# StickSoc_Left.net
KiCad netlist of a schematic drawn in EAGLE
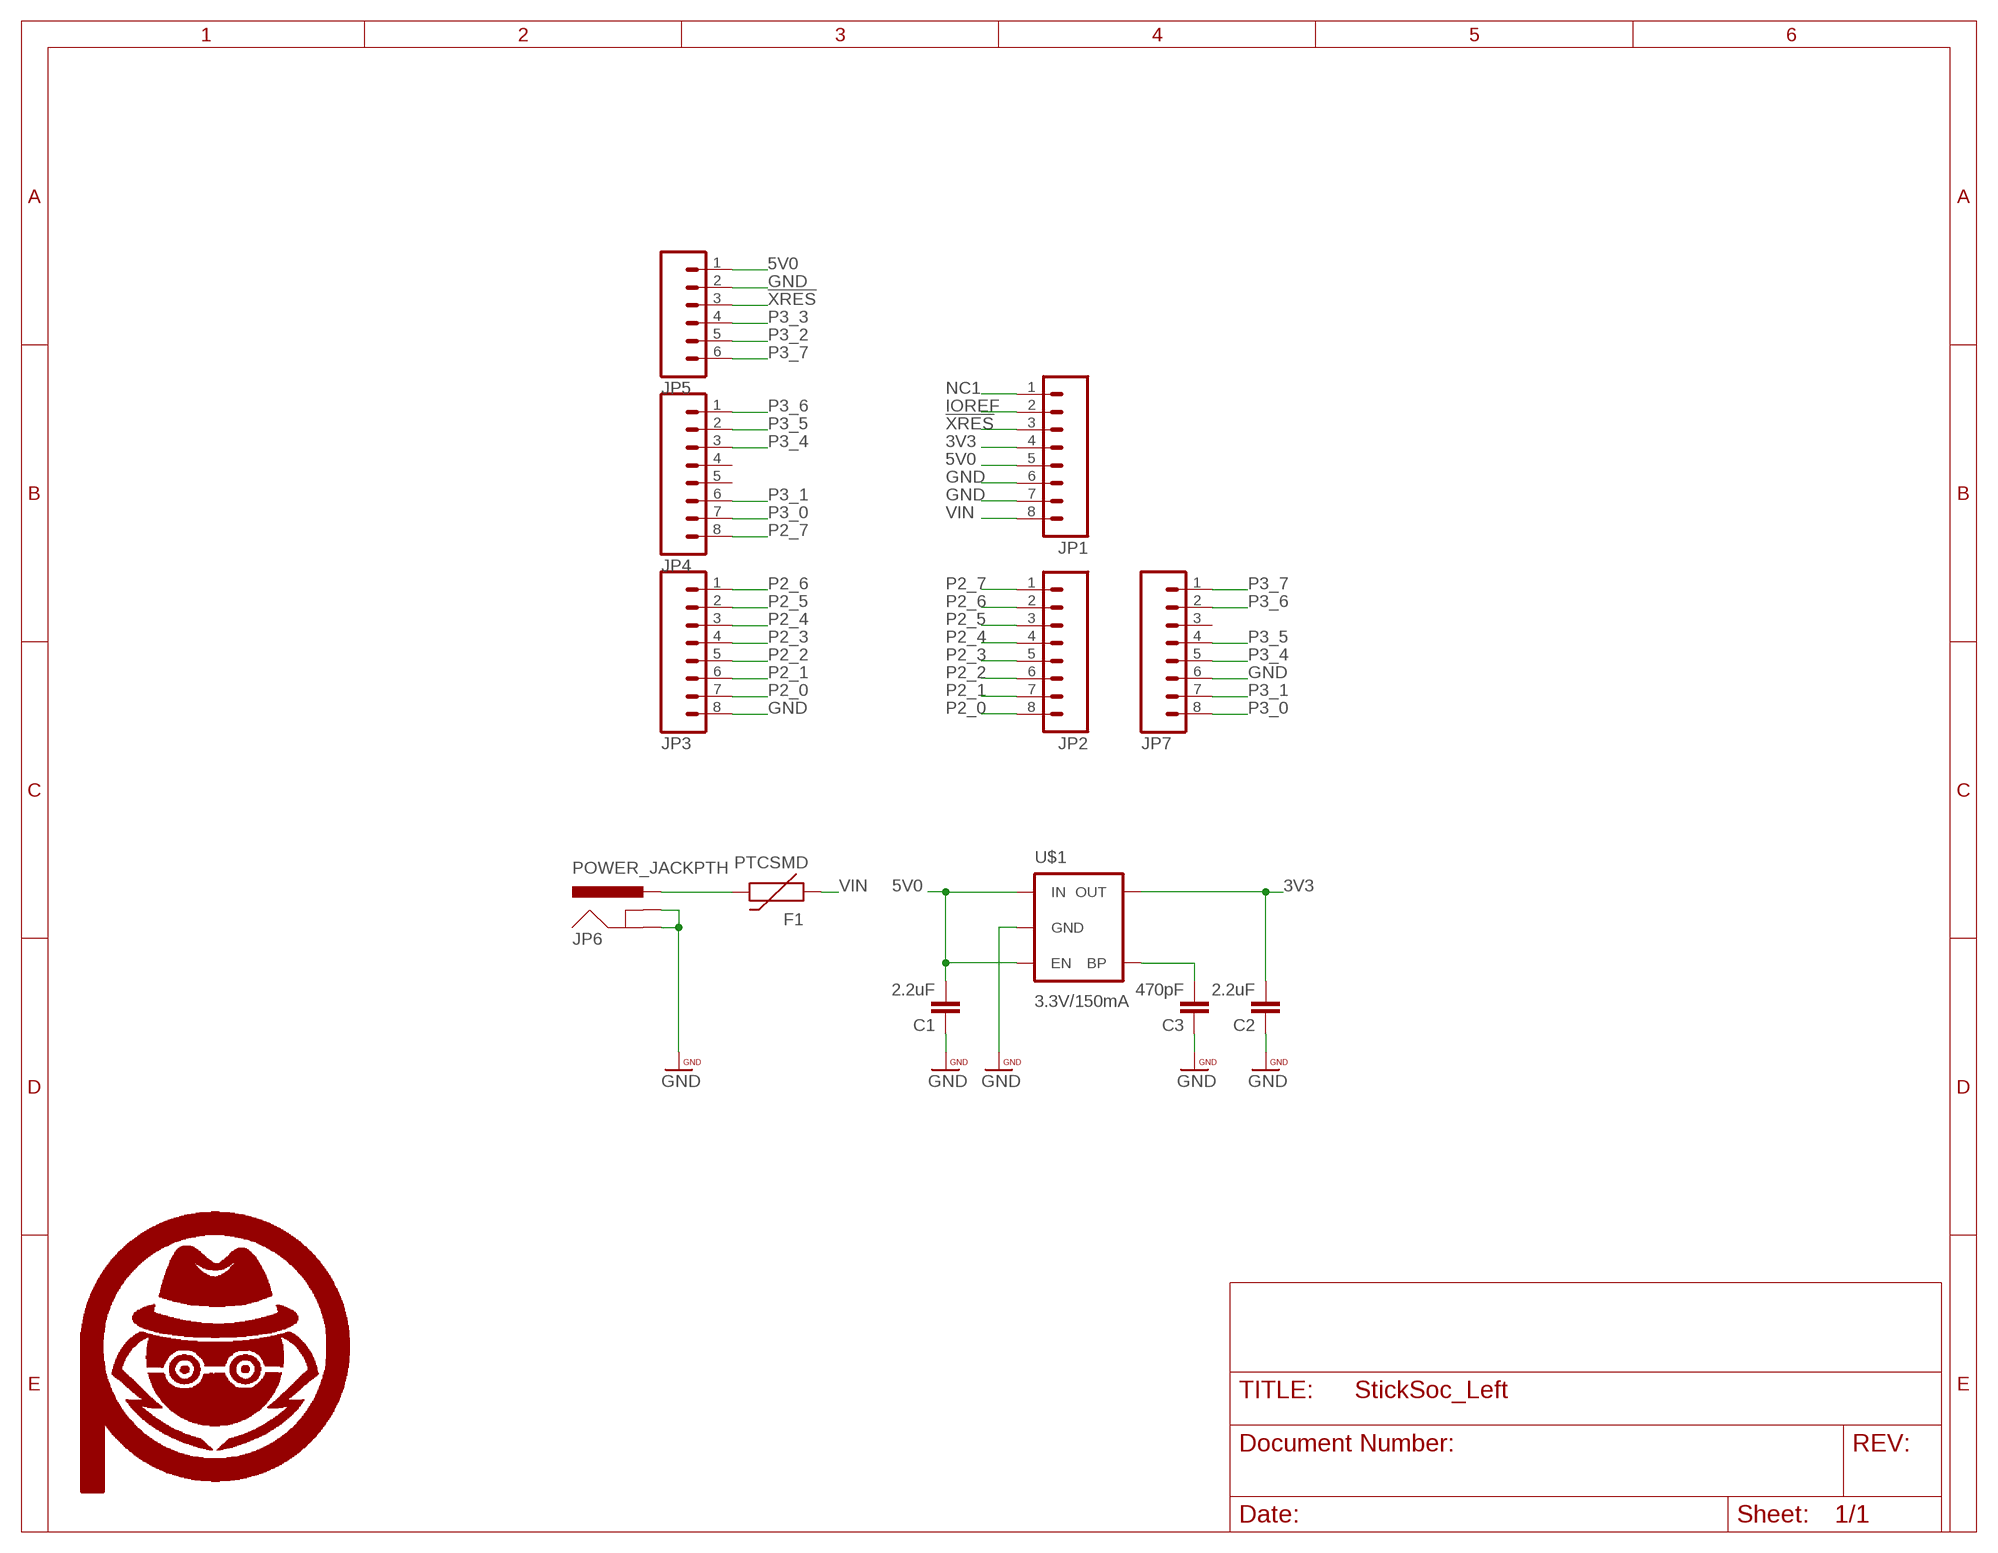
[diagram p0: schematic, sheet 1]

(export (version "E")
  (design (tool "Eeschema 10.0.6"))
  (components
    (comp (ref "C1")
      (value "2.2uF")
      (footprint "eagle-import:0805")
      (libsource (lib "eagle-import") (part "CAP0805"))
    )
    (comp (ref "C2")
      (value "2.2uF")
      (footprint "eagle-import:0805")
      (libsource (lib "eagle-import") (part "CAP0805"))
    )
    (comp (ref "C3")
      (value "470pF")
      (footprint "eagle-import:0805")
      (libsource (lib "eagle-import") (part "CAP0805"))
    )
    (comp (ref "F1")
      (value "PTCSMD")
      (footprint "eagle-import:PTC-1206")
      (libsource (lib "eagle-import") (part "PTCSMD"))
    )
    (comp (ref "JP1")
      (value "M081X08")
      (footprint "eagle-import:1X08")
      (libsource (lib "eagle-import") (part "M081X08"))
    )
    (comp (ref "JP2")
      (value "M081X08")
      (footprint "eagle-import:1X08")
      (libsource (lib "eagle-import") (part "M081X08"))
    )
    (comp (ref "JP3")
      (value "M081X08")
      (footprint "eagle-import:1X08")
      (libsource (lib "eagle-import") (part "M081X08"))
    )
    (comp (ref "JP4")
      (value "M081X08")
      (footprint "eagle-import:1X08")
      (libsource (lib "eagle-import") (part "M081X08"))
    )
    (comp (ref "JP5")
      (value "M06SIP")
      (footprint "eagle-import:1X06")
      (libsource (lib "eagle-import") (part "M06SIP"))
    )
    (comp (ref "JP6")
      (value "POWER_JACKPTH")
      (footprint "eagle-import:POWER_JACK_PTH")
      (libsource (lib "eagle-import") (part "POWER_JACKPTH"))
    )
    (comp (ref "JP7")
      (value "M081X08")
      (footprint "eagle-import:1X08")
      (libsource (lib "eagle-import") (part "M081X08"))
    )
    (comp (ref "U$1")
      (value "3.3V/150mA")
      (footprint "eagle-import:SOT23-5")
      (libsource (lib "eagle-import") (part "V_REG_MIC52053.3V"))
    )
    (comp (ref "U$7")
      (value "PA_LOGO_SYMSMALL")
      (footprint "eagle-import:PA_LOGO_AGENT_SMALL_SYM")
      (libsource (lib "eagle-import") (part "PA_LOGO_SYMSMALL"))
    )
    (comp (ref "U$8")
      (value "PA_LOGO_SYMSMALL")
      (footprint "eagle-import:PA_LOGO_AGENT_SMALL_SYM")
      (libsource (lib "eagle-import") (part "PA_LOGO_SYMSMALL"))
    )
  )
  (nets
    (net (code "1") (name "/3V3") (class "Default")
      (node (ref "C2") (pin "2") (pinfunction "2_2") (pintype "passive"))
      (node (ref "JP1") (pin "4") (pinfunction "4_4") (pintype "passive"))
      (node (ref "U$1") (pin "5") (pinfunction "OUT_5") (pintype "passive"))
    )
    (net (code "2") (name "/5V0") (class "Default")
      (node (ref "C1") (pin "2") (pinfunction "2_2") (pintype "passive"))
      (node (ref "JP1") (pin "5") (pinfunction "5_5") (pintype "passive"))
      (node (ref "JP5") (pin "1") (pinfunction "1_1") (pintype "passive"))
      (node (ref "U$1") (pin "1") (pinfunction "IN_1") (pintype "input"))
      (node (ref "U$1") (pin "3") (pinfunction "EN_3") (pintype "input"))
    )
    (net (code "3") (name "/IOREF") (class "Default")
      (node (ref "JP1") (pin "2") (pinfunction "2_2") (pintype "passive"))
    )
    (net (code "4") (name "/NC1") (class "Default")
      (node (ref "JP1") (pin "1") (pinfunction "1_1") (pintype "passive"))
    )
    (net (code "5") (name "/P2_0") (class "Default")
      (node (ref "JP2") (pin "8") (pinfunction "8_8") (pintype "passive"))
      (node (ref "JP3") (pin "7") (pinfunction "7_7") (pintype "passive"))
    )
    (net (code "6") (name "/P2_1") (class "Default")
      (node (ref "JP2") (pin "7") (pinfunction "7_7") (pintype "passive"))
      (node (ref "JP3") (pin "6") (pinfunction "6_6") (pintype "passive"))
    )
    (net (code "7") (name "/P2_2") (class "Default")
      (node (ref "JP2") (pin "6") (pinfunction "6_6") (pintype "passive"))
      (node (ref "JP3") (pin "5") (pinfunction "5_5") (pintype "passive"))
    )
    (net (code "8") (name "/P2_3") (class "Default")
      (node (ref "JP2") (pin "5") (pinfunction "5_5") (pintype "passive"))
      (node (ref "JP3") (pin "4") (pinfunction "4_4") (pintype "passive"))
    )
    (net (code "9") (name "/P2_4") (class "Default")
      (node (ref "JP2") (pin "4") (pinfunction "4_4") (pintype "passive"))
      (node (ref "JP3") (pin "3") (pinfunction "3_3") (pintype "passive"))
    )
    (net (code "10") (name "/P2_5") (class "Default")
      (node (ref "JP2") (pin "3") (pinfunction "3_3") (pintype "passive"))
      (node (ref "JP3") (pin "2") (pinfunction "2_2") (pintype "passive"))
    )
    (net (code "11") (name "/P2_6") (class "Default")
      (node (ref "JP2") (pin "2") (pinfunction "2_2") (pintype "passive"))
      (node (ref "JP3") (pin "1") (pinfunction "1_1") (pintype "passive"))
    )
    (net (code "12") (name "/P2_7") (class "Default")
      (node (ref "JP2") (pin "1") (pinfunction "1_1") (pintype "passive"))
      (node (ref "JP4") (pin "8") (pinfunction "8_8") (pintype "passive"))
    )
    (net (code "13") (name "/P3_0") (class "Default")
      (node (ref "JP4") (pin "7") (pinfunction "7_7") (pintype "passive"))
      (node (ref "JP7") (pin "8") (pinfunction "8_8") (pintype "passive"))
    )
    (net (code "14") (name "/P3_1") (class "Default")
      (node (ref "JP4") (pin "6") (pinfunction "6_6") (pintype "passive"))
      (node (ref "JP7") (pin "7") (pinfunction "7_7") (pintype "passive"))
    )
    (net (code "15") (name "/P3_2") (class "Default")
      (node (ref "JP5") (pin "5") (pinfunction "5_5") (pintype "passive"))
    )
    (net (code "16") (name "/P3_3") (class "Default")
      (node (ref "JP5") (pin "4") (pinfunction "4_4") (pintype "passive"))
    )
    (net (code "17") (name "/P3_4") (class "Default")
      (node (ref "JP4") (pin "3") (pinfunction "3_3") (pintype "passive"))
      (node (ref "JP7") (pin "5") (pinfunction "5_5") (pintype "passive"))
    )
    (net (code "18") (name "/P3_5") (class "Default")
      (node (ref "JP4") (pin "2") (pinfunction "2_2") (pintype "passive"))
      (node (ref "JP7") (pin "4") (pinfunction "4_4") (pintype "passive"))
    )
    (net (code "19") (name "/P3_6") (class "Default")
      (node (ref "JP4") (pin "1") (pinfunction "1_1") (pintype "passive"))
      (node (ref "JP7") (pin "2") (pinfunction "2_2") (pintype "passive"))
    )
    (net (code "20") (name "/P3_7") (class "Default")
      (node (ref "JP5") (pin "6") (pinfunction "6_6") (pintype "passive"))
      (node (ref "JP7") (pin "1") (pinfunction "1_1") (pintype "passive"))
    )
    (net (code "21") (name "/VIN") (class "Default")
      (node (ref "F1") (pin "1") (pinfunction "1_1") (pintype "bidirectional"))
      (node (ref "JP1") (pin "8") (pinfunction "8_8") (pintype "passive"))
    )
    (net (code "22") (name "/~{XRES}") (class "Default")
      (node (ref "JP1") (pin "3") (pinfunction "3_3") (pintype "passive"))
      (node (ref "JP5") (pin "3") (pinfunction "3_3") (pintype "passive"))
    )
    (net (code "23") (name "GND") (class "Default")
      (node (ref "C1") (pin "1") (pinfunction "1_1") (pintype "passive"))
      (node (ref "C2") (pin "1") (pinfunction "1_1") (pintype "passive"))
      (node (ref "C3") (pin "1") (pinfunction "1_1") (pintype "passive"))
      (node (ref "JP1") (pin "6") (pinfunction "6_6") (pintype "passive"))
      (node (ref "JP1") (pin "7") (pinfunction "7_7") (pintype "passive"))
      (node (ref "JP3") (pin "8") (pinfunction "8_8") (pintype "passive"))
      (node (ref "JP5") (pin "2") (pinfunction "2_2") (pintype "passive"))
      (node (ref "JP6") (pin "GND") (pinfunction "GND_GND") (pintype "bidirectional"))
      (node (ref "JP6") (pin "GNDBREAK") (pinfunction "GNDBREAK_GNDBREAK") (pintype "bidirectional"))
      (node (ref "JP7") (pin "6") (pinfunction "6_6") (pintype "passive"))
      (node (ref "U$1") (pin "2") (pinfunction "GND_2") (pintype "input"))
    )
    (net (code "24") (name "Net-(F1-Pad2)") (class "Default")
      (node (ref "F1") (pin "2") (pinfunction "2_2") (pintype "bidirectional"))
      (node (ref "JP6") (pin "PWR") (pinfunction "PWR_PWR") (pintype "bidirectional"))
    )
    (net (code "25") (name "Net-(U$1-BP)") (class "Default")
      (node (ref "C3") (pin "2") (pinfunction "2_2") (pintype "passive"))
      (node (ref "U$1") (pin "4") (pinfunction "BP_4") (pintype "input"))
    )
    (net (code "26") (name "unconnected-(JP4-Pad4)") (class "Default")
      (node (ref "JP4") (pin "4") (pinfunction "4_4") (pintype "passive"))
    )
    (net (code "27") (name "unconnected-(JP4-Pad5)") (class "Default")
      (node (ref "JP4") (pin "5") (pinfunction "5_5") (pintype "passive"))
    )
    (net (code "28") (name "unconnected-(JP7-Pad3)") (class "Default")
      (node (ref "JP7") (pin "3") (pinfunction "3_3") (pintype "passive"))
    )
  )
)
